# PWR_REG_LED_Sheet.net
KiCad netlist of a schematic drawn in Altium Designer
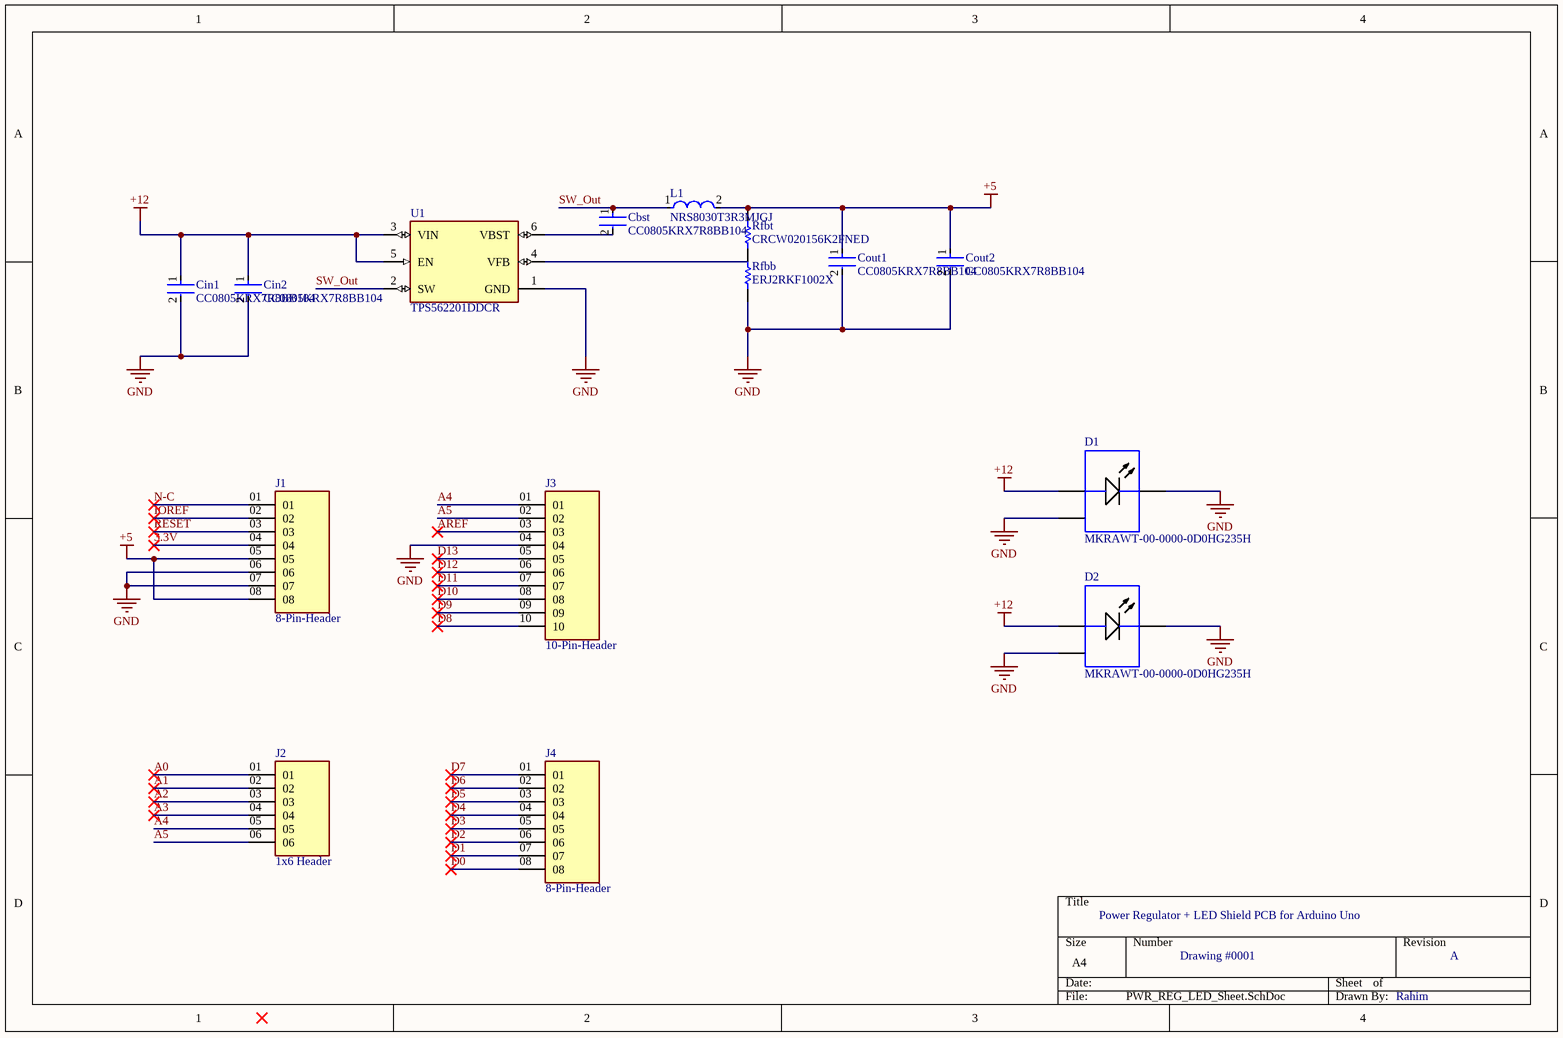
[diagram p0: PWR_REG_LED_Sheet.SchDoc]

(export (version "E")
  (design (tool "Eeschema 10.0.6"))
  (components
    (comp (ref "Cbst")
      (value "CC0805KRX7R8BB104")
      (footprint "FP-CC0805-0_85-MFG")
      (description "CAP CER 0.1UF 25V X7R 0805")
      (fields (field (name "TOLERANCE") "0.1") (field (name "MANUFACTURER") "Yageo"))
      (libsource (lib "Altium Content Vault") (part "11868f565c42a9108669ba33697ecf6"))
    )
    (comp (ref "Cin1")
      (value "CC0805KRX7R8BB104")
      (footprint "FP-CC0805-0_85-MFG")
      (description "CAP CER 0.1UF 25V X7R 0805")
      (fields (field (name "TOLERANCE") "0.1") (field (name "MANUFACTURER") "Yageo"))
      (libsource (lib "Altium Content Vault") (part "11868f565c42a9108669ba33697ecf6"))
    )
    (comp (ref "Cin2")
      (value "CC0805KRX7R8BB104")
      (footprint "FP-CC0805-0_85-MFG")
      (description "CAP CER 0.1UF 25V X7R 0805")
      (fields (field (name "TOLERANCE") "0.1") (field (name "MANUFACTURER") "Yageo"))
      (libsource (lib "Altium Content Vault") (part "11868f565c42a9108669ba33697ecf6"))
    )
    (comp (ref "Cout1")
      (value "CC0805KRX7R8BB104")
      (footprint "FP-CC0805-0_85-MFG")
      (description "CAP CER 0.1UF 25V X7R 0805")
      (fields (field (name "TOLERANCE") "0.1") (field (name "MANUFACTURER") "Yageo"))
      (libsource (lib "Altium Content Vault") (part "11868f565c42a9108669ba33697ecf6"))
    )
    (comp (ref "Cout2")
      (value "CC0805KRX7R8BB104")
      (footprint "FP-CC0805-0_85-MFG")
      (description "CAP CER 0.1UF 25V X7R 0805")
      (fields (field (name "TOLERANCE") "0.1") (field (name "MANUFACTURER") "Yageo"))
      (libsource (lib "Altium Content Vault") (part "11868f565c42a9108669ba33697ecf6"))
    )
    (comp (ref "D1")
      (value "MKRAWT-00-0000-0D0HG235H")
      (footprint "CREE-MK-R-2_V")
      (description "LED, White, 12 V, 2-Pin SMD, RoHS, Tape and Reel")
      (libsource (lib "Altium Content Vault") (part "LED_WHITE-3"))
    )
    (comp (ref "D2")
      (value "MKRAWT-00-0000-0D0HG235H")
      (footprint "CREE-MK-R-2_V")
      (description "LED, White, 12 V, 2-Pin SMD, RoHS, Tape and Reel")
      (libsource (lib "Altium Content Vault") (part "LED_WHITE-3"))
    )
    (comp (ref "J1")
      (value "8-Pin-Header")
      (footprint "SAMTEC_SSQ-108-03-X-S")
      (description "8 Position Receptacle Connector Through Hole, Right Angle")
      (fields (field (name "MF") "Samtec") (field (name "MP") "SSQ-108-03-L-S"))
      (libsource (lib "SSQ-108-03-X-S") (part "SSQ-108-03-X-S"))
    )
    (comp (ref "J2")
      (value "1x6 Header")
      (footprint "SAMTEC_SSQ-106-03-X-S")
      (description "6 Position Receptacle Connector Through Hole")
      (fields (field (name "MP") "SSQ-106-03-L-S") (field (name "MF") "Samtec"))
      (libsource (lib "SSQ-106-03-X-S") (part "SSQ-106-03-X-S"))
    )
    (comp (ref "J3")
      (value "10-Pin-Header")
      (footprint "SAMTEC_SSQ-110-03-X-S")
      (description "10 Position Receptacle Connector Through Hole, Right Angle")
      (fields (field (name "MF") "Samtec") (field (name "MP") "SSQ-110-03-L-S"))
      (libsource (lib "SSQ-110-03-X-S") (part "SSQ-110-03-X-S"))
    )
    (comp (ref "J4")
      (value "8-Pin-Header")
      (footprint "SAMTEC_SSQ-108-03-X-S")
      (description "8 Position Receptacle Connector Through Hole, Right Angle")
      (fields (field (name "MF") "Samtec") (field (name "MP") "SSQ-108-03-L-S"))
      (libsource (lib "SSQ-108-03-X-S") (part "SSQ-108-03-X-S"))
    )
    (comp (ref "L1")
      (value "NRS8030T3R3MJGJ")
      (footprint "FP-NRS8030-MFG")
      (description "Inductor Power Shielded Wirewound 3.3uH 20% 100KHz Ferrite 4.2A 24.7mΩ DCR T/R")
      (fields (field (name "TOLERANCE") "20%"))
      (libsource (lib "Altium Content Vault") (part "725321dda6339637d4d059423bc1c3c"))
    )
    (comp (ref "Rfbb")
      (value "ERJ2RKF1002X")
      (footprint "RESC1005X40X25LL05T05")
      (description "Chip Resistor, 10 KOhm, +/- 1%, 0.1 W, -55 to 155 degC, 0402 (1005 Metric), RoHS, Tape and Reel")
      (fields (field (name "TOLERANCE") "1%") (field (name "MANUFACTURER") "Panasonic"))
      (libsource (lib "Altium Content Vault") (part "RES-2"))
    )
    (comp (ref "Rfbt")
      (value "CRCW020156K2FNED")
      (footprint "RESC0603X28X15NL05T05")
      (fields (field (name "MANUFACTURER") "Vishay Dale"))
      (libsource (lib "Altium Content Vault") (part "RES"))
    )
    (comp (ref "U1")
      (value "TPS562201DDCR")
      (footprint "FP-DDC0006A-IPC_C")
      (description "IC REG BUCK ADJ 2A TSOT23-6")
      (libsource (lib "Altium Content Vault") (part "957e164956730ea4bf6293280af19fc"))
    )
  )
  (nets
    (net (code "1") (name "+5") (class "Default")
      (node (ref "Cout1") (pin "1") (pinfunction "1_1") (pintype "passive"))
      (node (ref "Cout2") (pin "1") (pinfunction "1_1") (pintype "passive"))
      (node (ref "J1") (pin "05") (pinfunction "05_05") (pintype "passive"))
      (node (ref "J1") (pin "08") (pinfunction "08_08") (pintype "passive"))
      (node (ref "L1") (pin "2") (pinfunction "2_2") (pintype "passive"))
      (node (ref "Rfbt") (pin "2") (pinfunction "2_2") (pintype "passive"))
    )
    (net (code "2") (name "+12") (class "Default")
      (node (ref "Cin1") (pin "1") (pinfunction "1_1") (pintype "passive"))
      (node (ref "Cin2") (pin "1") (pinfunction "1_1") (pintype "passive"))
      (node (ref "D1") (pin "1") (pinfunction "A_1") (pintype "passive"))
      (node (ref "D2") (pin "1") (pinfunction "A_1") (pintype "passive"))
      (node (ref "U1") (pin "3") (pinfunction "VIN_3") (pintype "bidirectional"))
      (node (ref "U1") (pin "5") (pinfunction "EN_5") (pintype "input"))
    )
    (net (code "3") (name "/3.3V") (class "Default")
      (node (ref "J1") (pin "04") (pinfunction "04_04") (pintype "passive+no_connect"))
    )
    (net (code "4") (name "/A0") (class "Default")
      (node (ref "J2") (pin "01") (pinfunction "01_01") (pintype "passive+no_connect"))
    )
    (net (code "5") (name "/A1") (class "Default")
      (node (ref "J2") (pin "02") (pinfunction "02_02") (pintype "passive+no_connect"))
    )
    (net (code "6") (name "/A2") (class "Default")
      (node (ref "J2") (pin "03") (pinfunction "03_03") (pintype "passive+no_connect"))
    )
    (net (code "7") (name "/A3") (class "Default")
      (node (ref "J2") (pin "04") (pinfunction "04_04") (pintype "passive+no_connect"))
    )
    (net (code "8") (name "/A4") (class "Default")
      (node (ref "J2") (pin "05") (pinfunction "05_05") (pintype "passive"))
      (node (ref "J3") (pin "01") (pinfunction "01_01") (pintype "passive"))
    )
    (net (code "9") (name "/A5") (class "Default")
      (node (ref "J2") (pin "06") (pinfunction "06_06") (pintype "passive"))
      (node (ref "J3") (pin "02") (pinfunction "02_02") (pintype "passive"))
    )
    (net (code "10") (name "/AREF") (class "Default")
      (node (ref "J3") (pin "03") (pinfunction "03_03") (pintype "passive+no_connect"))
    )
    (net (code "11") (name "/D0") (class "Default")
      (node (ref "J4") (pin "08") (pinfunction "08_08") (pintype "passive+no_connect"))
    )
    (net (code "12") (name "/D1") (class "Default")
      (node (ref "J4") (pin "07") (pinfunction "07_07") (pintype "passive+no_connect"))
    )
    (net (code "13") (name "/D2") (class "Default")
      (node (ref "J4") (pin "06") (pinfunction "06_06") (pintype "passive+no_connect"))
    )
    (net (code "14") (name "/D3") (class "Default")
      (node (ref "J4") (pin "05") (pinfunction "05_05") (pintype "passive+no_connect"))
    )
    (net (code "15") (name "/D4") (class "Default")
      (node (ref "J4") (pin "04") (pinfunction "04_04") (pintype "passive+no_connect"))
    )
    (net (code "16") (name "/D5") (class "Default")
      (node (ref "J4") (pin "03") (pinfunction "03_03") (pintype "passive+no_connect"))
    )
    (net (code "17") (name "/D6") (class "Default")
      (node (ref "J4") (pin "02") (pinfunction "02_02") (pintype "passive+no_connect"))
    )
    (net (code "18") (name "/D7") (class "Default")
      (node (ref "J4") (pin "01") (pinfunction "01_01") (pintype "passive+no_connect"))
    )
    (net (code "19") (name "/D8") (class "Default")
      (node (ref "J3") (pin "10") (pinfunction "10_10") (pintype "passive+no_connect"))
    )
    (net (code "20") (name "/D9") (class "Default")
      (node (ref "J3") (pin "09") (pinfunction "09_09") (pintype "passive+no_connect"))
    )
    (net (code "21") (name "/D10") (class "Default")
      (node (ref "J3") (pin "08") (pinfunction "08_08") (pintype "passive+no_connect"))
    )
    (net (code "22") (name "/D11") (class "Default")
      (node (ref "J3") (pin "07") (pinfunction "07_07") (pintype "passive+no_connect"))
    )
    (net (code "23") (name "/D12") (class "Default")
      (node (ref "J3") (pin "06") (pinfunction "06_06") (pintype "passive+no_connect"))
    )
    (net (code "24") (name "/D13") (class "Default")
      (node (ref "J3") (pin "05") (pinfunction "05_05") (pintype "passive+no_connect"))
    )
    (net (code "25") (name "/IOREF") (class "Default")
      (node (ref "J1") (pin "02") (pinfunction "02_02") (pintype "passive+no_connect"))
    )
    (net (code "26") (name "/N-C") (class "Default")
      (node (ref "J1") (pin "01") (pinfunction "01_01") (pintype "passive+no_connect"))
    )
    (net (code "27") (name "/RESET") (class "Default")
      (node (ref "J1") (pin "03") (pinfunction "03_03") (pintype "passive+no_connect"))
    )
    (net (code "28") (name "/SW_Out") (class "Default")
      (node (ref "Cbst") (pin "1") (pinfunction "1_1") (pintype "passive"))
      (node (ref "L1") (pin "1") (pinfunction "1_1") (pintype "passive"))
      (node (ref "U1") (pin "2") (pinfunction "SW_2") (pintype "bidirectional"))
    )
    (net (code "29") (name "GND") (class "Default")
      (node (ref "Cin1") (pin "2") (pinfunction "2_2") (pintype "passive"))
      (node (ref "Cin2") (pin "2") (pinfunction "2_2") (pintype "passive"))
      (node (ref "Cout1") (pin "2") (pinfunction "2_2") (pintype "passive"))
      (node (ref "Cout2") (pin "2") (pinfunction "2_2") (pintype "passive"))
      (node (ref "D1") (pin "2") (pinfunction "K_2") (pintype "passive"))
      (node (ref "D1") (pin "3") (pinfunction "EP_3") (pintype "passive"))
      (node (ref "D2") (pin "2") (pinfunction "K_2") (pintype "passive"))
      (node (ref "D2") (pin "3") (pinfunction "EP_3") (pintype "passive"))
      (node (ref "J1") (pin "06") (pinfunction "06_06") (pintype "passive"))
      (node (ref "J1") (pin "07") (pinfunction "07_07") (pintype "passive"))
      (node (ref "J3") (pin "04") (pinfunction "04_04") (pintype "passive"))
      (node (ref "Rfbb") (pin "1") (pinfunction "1_1") (pintype "passive"))
      (node (ref "U1") (pin "1") (pinfunction "GND_1") (pintype "power_in"))
    )
    (net (code "30") (name "Net-(U1-VBST)") (class "Default")
      (node (ref "Cbst") (pin "2") (pinfunction "2_2") (pintype "passive"))
      (node (ref "U1") (pin "6") (pinfunction "VBST_6") (pintype "bidirectional"))
    )
    (net (code "31") (name "Net-(U1-VFB)") (class "Default")
      (node (ref "Rfbt") (pin "1") (pinfunction "1_1") (pintype "passive"))
      (node (ref "U1") (pin "4") (pinfunction "VFB_4") (pintype "bidirectional"))
    )
    (net (code "32") (name "unconnected-(Rfbb-Pad2)") (class "Default")
      (node (ref "Rfbb") (pin "2") (pinfunction "2_2") (pintype "passive"))
    )
  )
)
